# Sheet6.net
KiCad netlist of a schematic drawn in Altium Designer
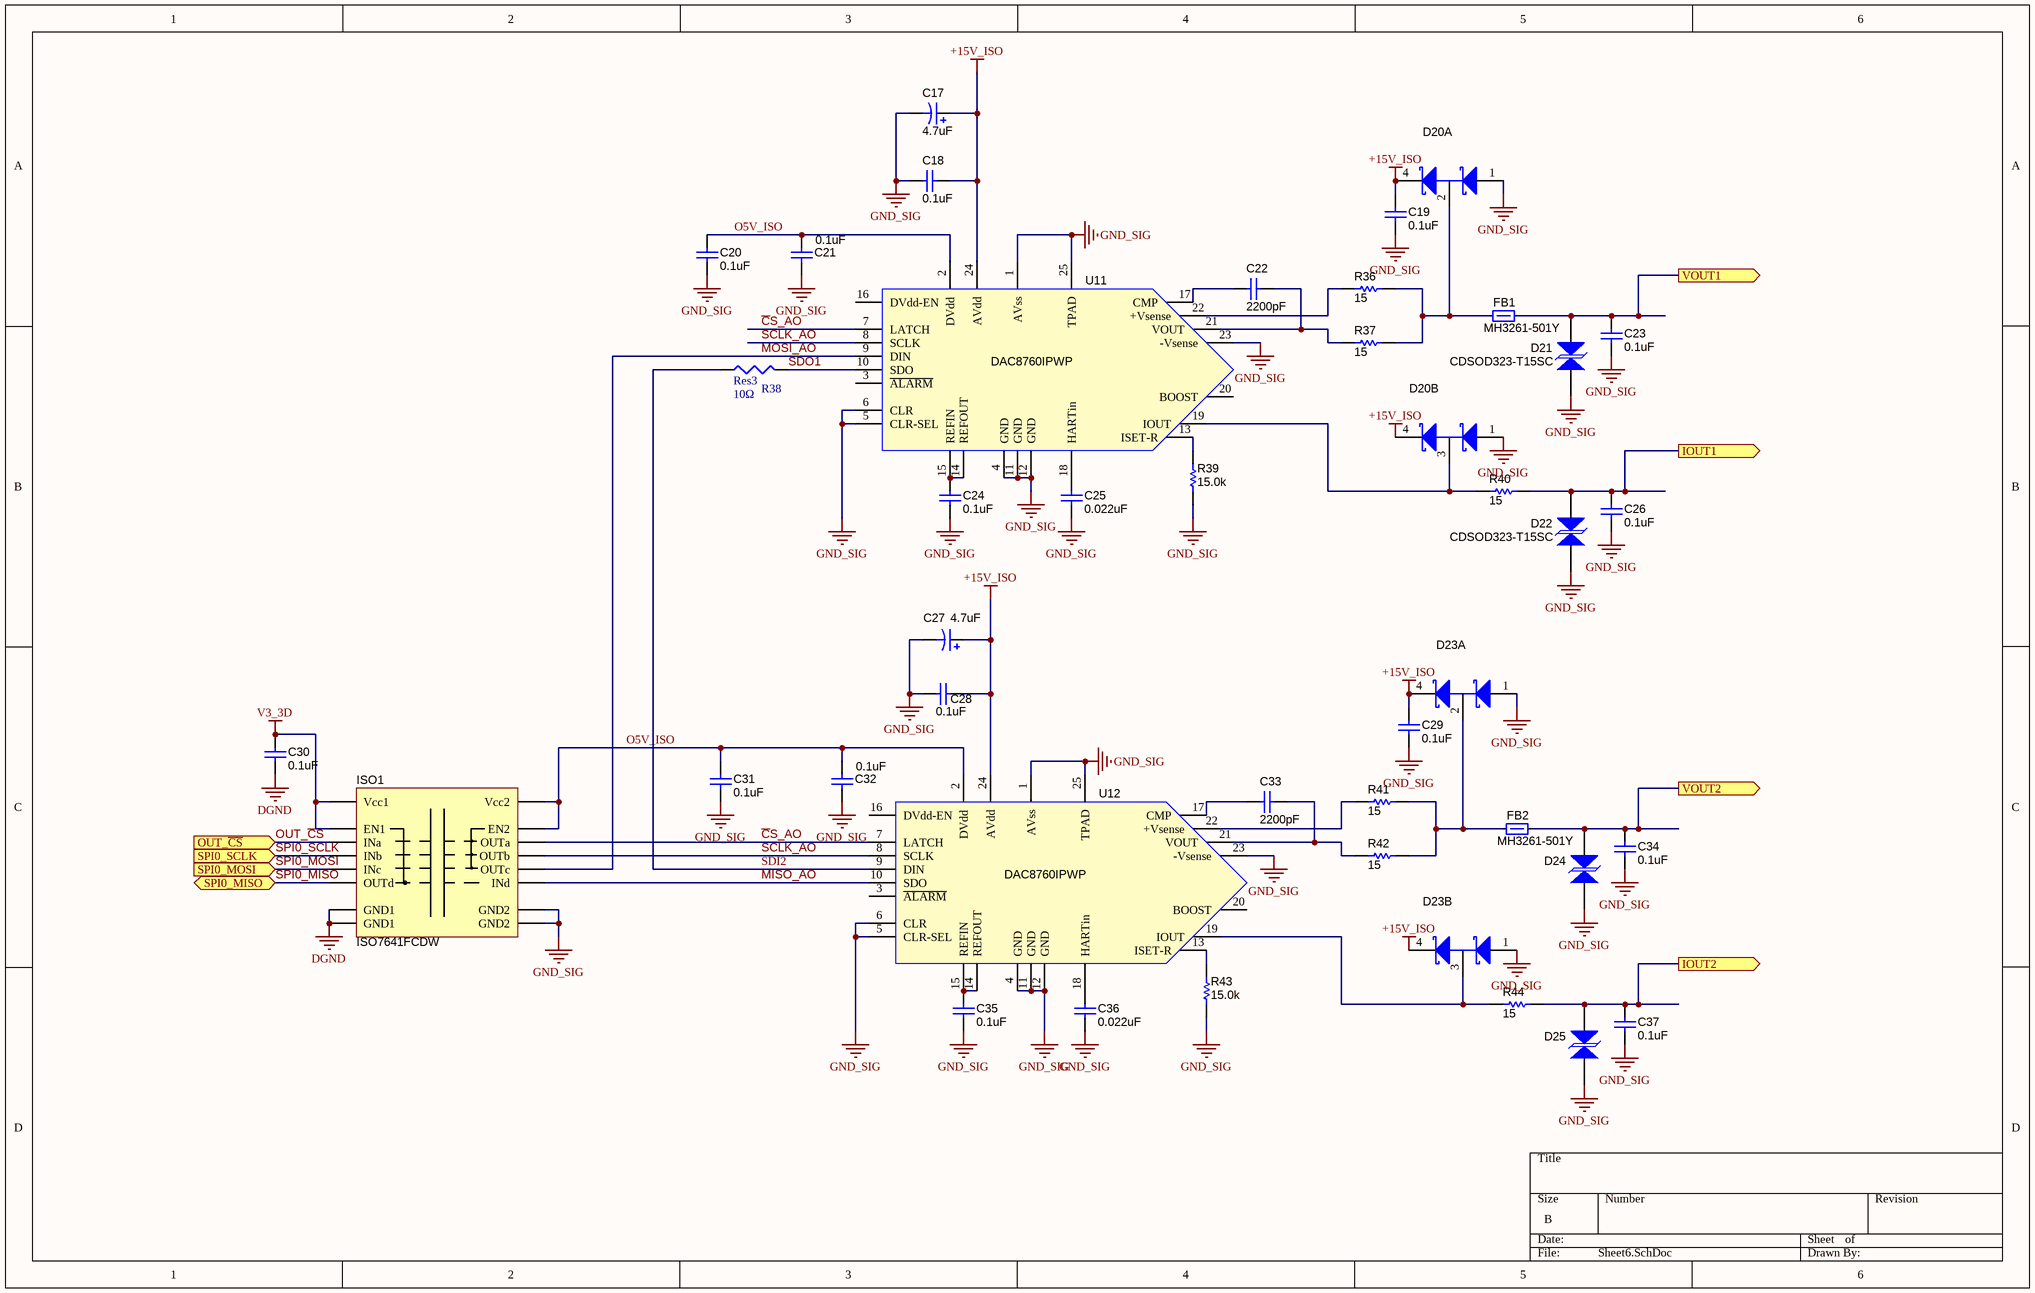
[diagram p0: Sheet6.SchDoc]

(export (version "E")
  (design (tool "Eeschema 10.0.6"))
  (components
    (comp (ref "C17")
      (value "293D475X9035C2TE3")
      (footprint "6032-28")
      (description "CAP, TA, 4.7uF, 35V, +/-10%, 1.9 ohm, SMD")
      (fields
        (field (name "VALUEDISPLAYED") "4.7uF")
        (field (name "MANUFACTURER") "Vishay-Sprague")
        (field (name "PUBLISHER") "Texas Instruments")
      )
      (libsource (lib "Capacitor_Tantalum") (part "293D475X9035C2TE3"))
    )
    (comp (ref "C18")
      (value "GRM188R71H104KA93D")
      (footprint "0805_cap")
      (description "CAP, CERM, 0.1uF, 50V, +/-10%, X7R, 0603")
      (fields
        (field (name "VALUEDISPLAYED") "0.1uF")
        (field (name "MANUFACTURER") "MuRata")
        (field (name "PUBLISHER") "Texas Instruments")
      )
      (libsource (lib "Capacitor_Ceramic") (part "GRM188R71H104KA93D"))
    )
    (comp (ref "C19")
      (value "GRM188R71H104KA93D")
      (footprint "0805_cap")
      (description "CAP, CERM, 0.1uF, 50V, +/-10%, X7R, 0603")
      (fields
        (field (name "VALUEDISPLAYED") "0.1uF")
        (field (name "MANUFACTURER") "MuRata")
        (field (name "PUBLISHER") "Texas Instruments")
      )
      (libsource (lib "Capacitor_Ceramic") (part "GRM188R71H104KA93D"))
    )
    (comp (ref "C20")
      (value "GRM188R71H104KA93D")
      (footprint "0805_cap")
      (description "CAP, CERM, 0.1uF, 50V, +/-10%, X7R, 0603")
      (fields
        (field (name "VALUEDISPLAYED") "0.1uF")
        (field (name "MANUFACTURER") "MuRata")
        (field (name "PUBLISHER") "Texas Instruments")
      )
      (libsource (lib "Capacitor_Ceramic") (part "GRM188R71H104KA93D"))
    )
    (comp (ref "C21")
      (value "GRM188R71H104KA93D")
      (footprint "0805_cap")
      (description "CAP, CERM, 0.1uF, 50V, +/-10%, X7R, 0603")
      (fields
        (field (name "VALUEDISPLAYED") "0.1uF")
        (field (name "MANUFACTURER") "MuRata")
        (field (name "PUBLISHER") "Texas Instruments")
      )
      (libsource (lib "Capacitor_Ceramic") (part "GRM188R71H104KA93D"))
    )
    (comp (ref "C22")
      (value "GRM1885C1H222JA01D")
      (footprint "0805_cap")
      (description "CAP, CERM, 2200pF, 50V, +/-5%, C0G/NP0, 0603")
      (fields
        (field (name "VALUEDISPLAYED") "2200pF")
        (field (name "MANUFACTURER") "MuRata")
        (field (name "PUBLISHER") "Texas Instruments")
      )
      (libsource (lib "Capacitor_Ceramic") (part "GRM1885C1H222JA01D"))
    )
    (comp (ref "C23")
      (value "06035C104KAT2A")
      (footprint "0805_cap")
      (description "CAP, CERM, 0.1uF, 50V, +/-10%, X7R, 0603")
      (fields
        (field (name "VALUEDISPLAYED") "0.1uF")
        (field (name "MANUFACTURER") "AVX")
        (field (name "PUBLISHER") "Texas Instruments")
      )
      (libsource (lib "Capacitor_Ceramic") (part "06035C104KAT2A"))
    )
    (comp (ref "C24")
      (value "06035C104KAT2A")
      (footprint "0805_cap")
      (description "CAP, CERM, 0.1uF, 50V, +/-10%, X7R, 0603")
      (fields
        (field (name "VALUEDISPLAYED") "0.1uF")
        (field (name "MANUFACTURER") "AVX")
        (field (name "PUBLISHER") "Texas Instruments")
      )
      (libsource (lib "Capacitor_Ceramic") (part "06035C104KAT2A"))
    )
    (comp (ref "C25")
      (value "C1608X7R1H223K")
      (footprint "0805_cap")
      (description "CAP, CERM, 0.022uF, 50V, +/-10%, X7R, 0603")
      (fields
        (field (name "VALUEDISPLAYED") "0.022uF")
        (field (name "MANUFACTURER") "TDK")
        (field (name "PUBLISHER") "Texas Instruments")
      )
      (libsource (lib "Capacitor_Ceramic") (part "C1608X7R1H223K"))
    )
    (comp (ref "C26")
      (value "06035C104KAT2A")
      (footprint "0805_cap")
      (description "CAP, CERM, 0.1uF, 50V, +/-10%, X7R, 0603")
      (fields
        (field (name "VALUEDISPLAYED") "0.1uF")
        (field (name "MANUFACTURER") "AVX")
        (field (name "PUBLISHER") "Texas Instruments")
      )
      (libsource (lib "Capacitor_Ceramic") (part "06035C104KAT2A"))
    )
    (comp (ref "C27")
      (value "293D475X9035C2TE3")
      (footprint "6032-28")
      (description "CAP, TA, 4.7uF, 35V, +/-10%, 1.9 ohm, SMD")
      (fields
        (field (name "VALUEDISPLAYED") "4.7uF")
        (field (name "MANUFACTURER") "Vishay-Sprague")
        (field (name "PUBLISHER") "Texas Instruments")
      )
      (libsource (lib "Capacitor_Tantalum") (part "293D475X9035C2TE3"))
    )
    (comp (ref "C28")
      (value "GRM188R71H104KA93D")
      (footprint "0805_cap")
      (description "CAP, CERM, 0.1uF, 50V, +/-10%, X7R, 0603")
      (fields
        (field (name "VALUEDISPLAYED") "0.1uF")
        (field (name "MANUFACTURER") "MuRata")
        (field (name "PUBLISHER") "Texas Instruments")
      )
      (libsource (lib "Capacitor_Ceramic") (part "GRM188R71H104KA93D"))
    )
    (comp (ref "C29")
      (value "GRM188R71H104KA93D")
      (footprint "0805_cap")
      (description "CAP, CERM, 0.1uF, 50V, +/-10%, X7R, 0603")
      (fields
        (field (name "VALUEDISPLAYED") "0.1uF")
        (field (name "MANUFACTURER") "MuRata")
        (field (name "PUBLISHER") "Texas Instruments")
      )
      (libsource (lib "Capacitor_Ceramic") (part "GRM188R71H104KA93D"))
    )
    (comp (ref "C30")
      (value "GRM188R71H104KA93D")
      (footprint "0805_cap")
      (description "CAP, CERM, 0.1uF, 50V, +/-10%, X7R, 0603")
      (fields
        (field (name "VALUEDISPLAYED") "0.1uF")
        (field (name "MANUFACTURER") "MuRata")
        (field (name "PUBLISHER") "Texas Instruments")
      )
      (libsource (lib "Capacitor_Ceramic") (part "GRM188R71H104KA93D"))
    )
    (comp (ref "C31")
      (value "GRM188R71H104KA93D")
      (footprint "0805_cap")
      (description "CAP, CERM, 0.1uF, 50V, +/-10%, X7R, 0603")
      (fields
        (field (name "VALUEDISPLAYED") "0.1uF")
        (field (name "MANUFACTURER") "MuRata")
        (field (name "PUBLISHER") "Texas Instruments")
      )
      (libsource (lib "Capacitor_Ceramic") (part "GRM188R71H104KA93D"))
    )
    (comp (ref "C32")
      (value "GRM188R71H104KA93D")
      (footprint "0805_cap")
      (description "CAP, CERM, 0.1uF, 50V, +/-10%, X7R, 0603")
      (fields
        (field (name "VALUEDISPLAYED") "0.1uF")
        (field (name "MANUFACTURER") "MuRata")
        (field (name "PUBLISHER") "Texas Instruments")
      )
      (libsource (lib "Capacitor_Ceramic") (part "GRM188R71H104KA93D"))
    )
    (comp (ref "C33")
      (value "GRM1885C1H222JA01D")
      (footprint "0805_cap")
      (description "CAP, CERM, 2200pF, 50V, +/-5%, C0G/NP0, 0603")
      (fields
        (field (name "VALUEDISPLAYED") "2200pF")
        (field (name "MANUFACTURER") "MuRata")
        (field (name "PUBLISHER") "Texas Instruments")
      )
      (libsource (lib "Capacitor_Ceramic") (part "GRM1885C1H222JA01D"))
    )
    (comp (ref "C34")
      (value "06035C104KAT2A")
      (footprint "0805_cap")
      (description "CAP, CERM, 0.1uF, 50V, +/-10%, X7R, 0603")
      (fields
        (field (name "VALUEDISPLAYED") "0.1uF")
        (field (name "MANUFACTURER") "AVX")
        (field (name "PUBLISHER") "Texas Instruments")
      )
      (libsource (lib "Capacitor_Ceramic") (part "06035C104KAT2A"))
    )
    (comp (ref "C35")
      (value "06035C104KAT2A")
      (footprint "0805_cap")
      (description "CAP, CERM, 0.1uF, 50V, +/-10%, X7R, 0603")
      (fields
        (field (name "VALUEDISPLAYED") "0.1uF")
        (field (name "MANUFACTURER") "AVX")
        (field (name "PUBLISHER") "Texas Instruments")
      )
      (libsource (lib "Capacitor_Ceramic") (part "06035C104KAT2A"))
    )
    (comp (ref "C36")
      (value "C1608X7R1H223K")
      (footprint "0805_cap")
      (description "CAP, CERM, 0.022uF, 50V, +/-10%, X7R, 0603")
      (fields
        (field (name "VALUEDISPLAYED") "0.022uF")
        (field (name "MANUFACTURER") "TDK")
        (field (name "PUBLISHER") "Texas Instruments")
      )
      (libsource (lib "Capacitor_Ceramic") (part "C1608X7R1H223K"))
    )
    (comp (ref "C37")
      (value "06035C104KAT2A")
      (footprint "0805_cap")
      (description "CAP, CERM, 0.1uF, 50V, +/-10%, X7R, 0603")
      (fields
        (field (name "VALUEDISPLAYED") "0.1uF")
        (field (name "MANUFACTURER") "AVX")
        (field (name "PUBLISHER") "Texas Instruments")
      )
      (libsource (lib "Capacitor_Ceramic") (part "06035C104KAT2A"))
    )
    (comp (ref "D20")
      (value "~")
      (footprint "SOT-143")
      (description "IC TVS ARRAY 2-LINE 70V SOT-143")
      (fields
        (field (name "MANUFACTURER") "Bourns")
        (field (name "PARTNUMBER") "CD143A-SR70")
        (field (name "SYMBOLCREATOR") "Use LDAP id")
      )
      (libsource (lib "DAC8760-Symbols") (part "CD143A-SR70"))
    )
    (comp (ref "D21")
      (value "CDSOD323-T15SC")
      (footprint "sod-323")
      (description "DIODE TVS ARRAY 15V SOD323")
      (fields (field (name "MANUFACTURER") "Bourns") (field (name "SYMBOLCREATOR") "Use LDAP id"))
      (libsource (lib "DAC8760-Symbols") (part "SMAJ15CA"))
    )
    (comp (ref "D22")
      (value "CDSOD323-T15SC")
      (footprint "sod-323")
      (description "DIODE TVS ARRAY 15V SOD323")
      (fields (field (name "MANUFACTURER") "Bourns") (field (name "SYMBOLCREATOR") "Use LDAP id"))
      (libsource (lib "DAC8760-Symbols") (part "SMAJ15CA"))
    )
    (comp (ref "D23")
      (value "~")
      (footprint "SOT-143")
      (description "IC TVS ARRAY 2-LINE 70V SOT-143")
      (fields
        (field (name "MANUFACTURER") "Bourns")
        (field (name "PARTNUMBER") "CD143A-SR70")
        (field (name "SYMBOLCREATOR") "Use LDAP id")
      )
      (libsource (lib "DAC8760-Symbols") (part "CD143A-SR70"))
    )
    (comp (ref "D24")
      (value "~")
      (footprint "sod-323")
      (description "DIODE TVS ARRAY 15V SOD323")
      (fields
        (field (name "MANUFACTURER") "Bourns")
        (field (name "PARTNUMBER") "CDSOD323-T15SC")
        (field (name "SYMBOLCREATOR") "Use LDAP id")
      )
      (libsource (lib "DAC8760-Symbols") (part "SMAJ15CA"))
    )
    (comp (ref "D25")
      (value "~")
      (footprint "sod-323")
      (description "DIODE TVS ARRAY 15V SOD323")
      (fields
        (field (name "MANUFACTURER") "Bourns")
        (field (name "PARTNUMBER") "CDSOD323-T15SC")
        (field (name "SYMBOLCREATOR") "Use LDAP id")
      )
      (libsource (lib "DAC8760-Symbols") (part "SMAJ15CA"))
    )
    (comp (ref "FB1")
      (value "MH3261-501Y")
      (footprint "1210")
      (description "BEAD FERRITE 500 OHM 3.0A 3216")
      (fields (field (name "MANUFACTURER") "Bourns Inc.") (field (name "PUBLISHER") "Texas Instruments"))
      (libsource (lib "MiscParts") (part "Ferrite_Bead"))
    )
    (comp (ref "FB2")
      (value "MH3261-501Y")
      (footprint "1210")
      (description "BEAD FERRITE 500 OHM 3.0A 3216")
      (fields (field (name "MANUFACTURER") "Bourns Inc.") (field (name "PUBLISHER") "Texas Instruments"))
      (libsource (lib "MiscParts") (part "Ferrite_Bead"))
    )
    (comp (ref "ISO1")
      (value "ISO7641FCDW")
      (footprint "M16B_N")
      (description "ISOLATOR DGTL 25MBPS 4CH 16SOIC")
      (fields
        (field (name "MANUFACTURER") "Texas Instruments Inc")
        (field (name "SYMBOLCREATOR") "Use LDAP id")
      )
      (libsource (lib "DAC8760-Symbols") (part "ISO7241"))
    )
    (comp (ref "R36")
      (value "15")
      (footprint "0805")
      (description "RES, 15 ohm, 5%, 0.1W, 0603")
      (fields
        (field (name "PARTNUMBER") "CRCW060315R0JNEA")
        (field (name "MANUFACTURER") "Vishay-Dale")
        (field (name "PUBLISHER") "Texas Instruments")
      )
      (libsource (lib "Resistor_0603") (part "CRCW060315R0JNEA"))
    )
    (comp (ref "R37")
      (value "15")
      (footprint "0805")
      (description "RES, 15 ohm, 5%, 0.1W, 0603")
      (fields
        (field (name "PARTNUMBER") "CRCW060315R0JNEA")
        (field (name "MANUFACTURER") "Vishay-Dale")
        (field (name "PUBLISHER") "Texas Instruments")
      )
      (libsource (lib "Resistor_0603") (part "CRCW060315R0JNEA"))
    )
    (comp (ref "R38")
      (value "Res3")
      (footprint "0805")
      (description "Resistor")
      (fields (field (name "ALTIUM_VALUE") "10Ω") (field (name "PUBLISHER") "Altium Limited"))
      (libsource (lib "Miscellaneous Devices") (part "Res3"))
    )
    (comp (ref "R39")
      (value "15.0k")
      (footprint "0805")
      (description "RES, 15.0k ohm, 0.1%, 0.1W, 0603")
      (fields
        (field (name "PARTNUMBER") "RT0603BRD0715KL")
        (field (name "MANUFACTURER") "Yageo America")
        (field (name "PUBLISHER") "Texas Instruments")
      )
      (libsource (lib "Resistor_0603") (part "RT0603BRD0715KL"))
    )
    (comp (ref "R40")
      (value "15")
      (footprint "1210")
      (description "RES 15 OHM 1W 5% 2512")
      (fields
        (field (name "PARTNUMBER") "RPC2512JT15R0")
        (field (name "MANUFACTURER") "Stackpole Electronics")
      )
      (libsource (lib "Resistor_OtherSMT") (part "CRA2512-FZ-R080ELF"))
    )
    (comp (ref "R41")
      (value "15")
      (footprint "0805")
      (description "RES, 15 ohm, 5%, 0.1W, 0603")
      (fields
        (field (name "PARTNUMBER") "CRCW060315R0JNEA")
        (field (name "MANUFACTURER") "Vishay-Dale")
        (field (name "PUBLISHER") "Texas Instruments")
      )
      (libsource (lib "Resistor_0603") (part "CRCW060315R0JNEA"))
    )
    (comp (ref "R42")
      (value "15")
      (footprint "0805")
      (description "RES, 15 ohm, 5%, 0.1W, 0603")
      (fields
        (field (name "PARTNUMBER") "CRCW060315R0JNEA")
        (field (name "MANUFACTURER") "Vishay-Dale")
        (field (name "PUBLISHER") "Texas Instruments")
      )
      (libsource (lib "Resistor_0603") (part "CRCW060315R0JNEA"))
    )
    (comp (ref "R43")
      (value "15.0k")
      (footprint "0805")
      (description "RES, 15.0k ohm, 0.1%, 0.1W, 0603")
      (fields
        (field (name "PARTNUMBER") "RT0603BRD0715KL")
        (field (name "MANUFACTURER") "Yageo America")
        (field (name "PUBLISHER") "Texas Instruments")
      )
      (libsource (lib "Resistor_0603") (part "RT0603BRD0715KL"))
    )
    (comp (ref "R44")
      (value "15")
      (footprint "1210")
      (description "RES 15 OHM 1W 5% 2512")
      (fields
        (field (name "PARTNUMBER") "RPC2512JT15R0")
        (field (name "MANUFACTURER") "Stackpole Electronics")
      )
      (libsource (lib "Resistor_OtherSMT") (part "CRA2512-FZ-R080ELF"))
    )
    (comp (ref "U11")
      (value "DAC8760IPWP")
      (footprint "PWP24-DIE84X166")
      (description "1-Channel, 16-Bit, Programmable Current/Voltage Output DAC for 4-20mA Current Loop Applications")
      (fields
        (field (name "MANUFACTURER") "Texas Instruments")
        (field (name "SYMBOLCREATOR") "x0120606")
        (field (name "PUBLISHER") "Texas Instruments")
      )
      (libsource (lib "dolphi_ecs") (part "DAC8760IPWP_1"))
    )
    (comp (ref "U12")
      (value "DAC8760IPWP")
      (footprint "PWP24-DIE84X166")
      (description "1-Channel, 16-Bit, Programmable Current/Voltage Output DAC for 4-20mA Current Loop Applications")
      (fields
        (field (name "MANUFACTURER") "Texas Instruments")
        (field (name "SYMBOLCREATOR") "x0120606")
        (field (name "PUBLISHER") "Texas Instruments")
      )
      (libsource (lib "dolphi_ecs") (part "DAC8760IPWP_1"))
    )
  )
  (nets
    (net (code "1") (name "+15V_ISO") (class "Default")
      (node (ref "C17") (pin "1") (pinfunction "+_1") (pintype "passive"))
      (node (ref "C18") (pin "1") (pinfunction "1_1") (pintype "passive"))
      (node (ref "C19") (pin "1") (pinfunction "1_1") (pintype "passive"))
      (node (ref "C27") (pin "1") (pinfunction "+_1") (pintype "passive"))
      (node (ref "C28") (pin "1") (pinfunction "1_1") (pintype "passive"))
      (node (ref "C29") (pin "1") (pinfunction "1_1") (pintype "passive"))
      (node (ref "D20") (pin "4") (pinfunction "4_4") (pintype "passive"))
      (node (ref "D23") (pin "4") (pinfunction "4_4") (pintype "passive"))
      (node (ref "U11") (pin "24") (pinfunction "AVdd_24") (pintype "passive"))
      (node (ref "U12") (pin "24") (pinfunction "AVdd_24") (pintype "passive"))
    )
    (net (code "2") (name "/IOUT1") (class "Default")
      (node (ref "C26") (pin "1") (pinfunction "1_1") (pintype "passive"))
      (node (ref "D22") (pin "1") (pinfunction "1_1") (pintype "passive"))
      (node (ref "R40") (pin "2") (pinfunction "2_2") (pintype "passive"))
    )
    (net (code "3") (name "/IOUT2") (class "Default")
      (node (ref "C37") (pin "1") (pinfunction "1_1") (pintype "passive"))
      (node (ref "D25") (pin "1") (pinfunction "1_1") (pintype "passive"))
      (node (ref "R44") (pin "2") (pinfunction "2_2") (pintype "passive"))
    )
    (net (code "4") (name "/MISO_AO") (class "Default")
      (node (ref "ISO1") (pin "11") (pinfunction "INd_11") (pintype "passive"))
      (node (ref "U12") (pin "10") (pinfunction "SDO_10") (pintype "passive"))
    )
    (net (code "5") (name "/MOSI_AO") (class "Default")
      (node (ref "ISO1") (pin "12") (pinfunction "OUTc_12") (pintype "passive"))
      (node (ref "U11") (pin "9") (pinfunction "DIN_9") (pintype "passive"))
    )
    (net (code "6") (name "/O5V_ISO") (class "Default")
      (node (ref "C20") (pin "1") (pinfunction "1_1") (pintype "passive"))
      (node (ref "C21") (pin "1") (pinfunction "1_1") (pintype "passive"))
      (node (ref "C31") (pin "1") (pinfunction "1_1") (pintype "passive"))
      (node (ref "C32") (pin "1") (pinfunction "1_1") (pintype "passive"))
      (node (ref "ISO1") (pin "10") (pinfunction "EN2_10") (pintype "passive"))
      (node (ref "ISO1") (pin "16") (pinfunction "Vcc2_16") (pintype "passive"))
      (node (ref "U11") (pin "2") (pinfunction "DVdd_2") (pintype "passive"))
      (node (ref "U12") (pin "2") (pinfunction "DVdd_2") (pintype "passive"))
    )
    (net (code "7") (name "/OUT_~{CS}") (class "Default")
      (node (ref "ISO1") (pin "3") (pinfunction "INa_3") (pintype "passive"))
    )
    (net (code "8") (name "/SCLK_AO") (class "Default")
      (node (ref "ISO1") (pin "13") (pinfunction "OUTb_13") (pintype "passive"))
      (node (ref "U11") (pin "8") (pinfunction "SCLK_8") (pintype "passive"))
      (node (ref "U12") (pin "8") (pinfunction "SCLK_8") (pintype "passive"))
    )
    (net (code "9") (name "/SDI2") (class "Default")
      (node (ref "R38") (pin "1") (pinfunction "1_1") (pintype "passive"))
      (node (ref "U12") (pin "9") (pinfunction "DIN_9") (pintype "passive"))
    )
    (net (code "10") (name "/SDO1") (class "Default")
      (node (ref "R38") (pin "2") (pinfunction "2_2") (pintype "passive"))
      (node (ref "U11") (pin "10") (pinfunction "SDO_10") (pintype "passive"))
    )
    (net (code "11") (name "/SPI0_MISO") (class "Default")
      (node (ref "ISO1") (pin "6") (pinfunction "OUTd_6") (pintype "passive"))
    )
    (net (code "12") (name "/SPI0_MOSI") (class "Default")
      (node (ref "ISO1") (pin "5") (pinfunction "INc_5") (pintype "passive"))
    )
    (net (code "13") (name "/SPI0_SCLK") (class "Default")
      (node (ref "ISO1") (pin "4") (pinfunction "INb_4") (pintype "passive"))
    )
    (net (code "14") (name "/VOUT1") (class "Default")
      (node (ref "C23") (pin "1") (pinfunction "1_1") (pintype "passive"))
      (node (ref "D21") (pin "1") (pinfunction "1_1") (pintype "passive"))
      (node (ref "FB1") (pin "2") (pinfunction "2_2") (pintype "passive"))
    )
    (net (code "15") (name "/VOUT2") (class "Default")
      (node (ref "C34") (pin "1") (pinfunction "1_1") (pintype "passive"))
      (node (ref "D24") (pin "1") (pinfunction "1_1") (pintype "passive"))
      (node (ref "FB2") (pin "2") (pinfunction "2_2") (pintype "passive"))
    )
    (net (code "16") (name "/~{C}S_AO") (class "Default")
      (node (ref "ISO1") (pin "14") (pinfunction "OUTa_14") (pintype "passive"))
      (node (ref "U11") (pin "7") (pinfunction "LATCH_7") (pintype "passive"))
      (node (ref "U12") (pin "7") (pinfunction "LATCH_7") (pintype "passive"))
    )
    (net (code "17") (name "DGND") (class "Default")
      (node (ref "C30") (pin "2") (pinfunction "2_2") (pintype "passive"))
      (node (ref "ISO1") (pin "2") (pinfunction "GND1_2") (pintype "passive"))
      (node (ref "ISO1") (pin "8") (pinfunction "GND1_8") (pintype "passive"))
    )
    (net (code "18") (name "GND_SIG") (class "Default")
      (node (ref "C17") (pin "2") (pinfunction "-_2") (pintype "passive"))
      (node (ref "C18") (pin "2") (pinfunction "2_2") (pintype "passive"))
      (node (ref "C19") (pin "2") (pinfunction "2_2") (pintype "passive"))
      (node (ref "C20") (pin "2") (pinfunction "2_2") (pintype "passive"))
      (node (ref "C21") (pin "2") (pinfunction "2_2") (pintype "passive"))
      (node (ref "C23") (pin "2") (pinfunction "2_2") (pintype "passive"))
      (node (ref "C24") (pin "2") (pinfunction "2_2") (pintype "passive"))
      (node (ref "C25") (pin "2") (pinfunction "2_2") (pintype "passive"))
      (node (ref "C26") (pin "2") (pinfunction "2_2") (pintype "passive"))
      (node (ref "C27") (pin "2") (pinfunction "-_2") (pintype "passive"))
      (node (ref "C28") (pin "2") (pinfunction "2_2") (pintype "passive"))
      (node (ref "C29") (pin "2") (pinfunction "2_2") (pintype "passive"))
      (node (ref "C31") (pin "2") (pinfunction "2_2") (pintype "passive"))
      (node (ref "C32") (pin "2") (pinfunction "2_2") (pintype "passive"))
      (node (ref "C34") (pin "2") (pinfunction "2_2") (pintype "passive"))
      (node (ref "C35") (pin "2") (pinfunction "2_2") (pintype "passive"))
      (node (ref "C36") (pin "2") (pinfunction "2_2") (pintype "passive"))
      (node (ref "C37") (pin "2") (pinfunction "2_2") (pintype "passive"))
      (node (ref "D20") (pin "1") (pinfunction "1_1") (pintype "passive"))
      (node (ref "D21") (pin "2") (pinfunction "2_2") (pintype "passive"))
      (node (ref "D22") (pin "2") (pinfunction "2_2") (pintype "passive"))
      (node (ref "D23") (pin "1") (pinfunction "1_1") (pintype "passive"))
      (node (ref "D24") (pin "2") (pinfunction "2_2") (pintype "passive"))
      (node (ref "D25") (pin "2") (pinfunction "2_2") (pintype "passive"))
      (node (ref "ISO1") (pin "15") (pinfunction "GND2_15") (pintype "passive"))
      (node (ref "ISO1") (pin "9") (pinfunction "GND2_9") (pintype "passive"))
      (node (ref "R39") (pin "1") (pinfunction "1_1") (pintype "passive"))
      (node (ref "R43") (pin "1") (pinfunction "1_1") (pintype "passive"))
      (node (ref "U11") (pin "1") (pinfunction "AVss_1") (pintype "passive"))
      (node (ref "U11") (pin "11") (pinfunction "GND_11") (pintype "passive"))
      (node (ref "U11") (pin "12") (pinfunction "GND_12") (pintype "passive"))
      (node (ref "U11") (pin "23") (pinfunction "-Vsense_23") (pintype "passive"))
      (node (ref "U11") (pin "25") (pinfunction "TPAD_25") (pintype "passive"))
      (node (ref "U11") (pin "4") (pinfunction "GND_4") (pintype "passive"))
      (node (ref "U11") (pin "5") (pinfunction "CLR-SEL_5") (pintype "passive"))
      (node (ref "U11") (pin "6") (pinfunction "CLR_6") (pintype "passive"))
      (node (ref "U12") (pin "1") (pinfunction "AVss_1") (pintype "passive"))
      (node (ref "U12") (pin "11") (pinfunction "GND_11") (pintype "passive"))
      (node (ref "U12") (pin "12") (pinfunction "GND_12") (pintype "passive"))
      (node (ref "U12") (pin "23") (pinfunction "-Vsense_23") (pintype "passive"))
      (node (ref "U12") (pin "25") (pinfunction "TPAD_25") (pintype "passive"))
      (node (ref "U12") (pin "4") (pinfunction "GND_4") (pintype "passive"))
      (node (ref "U12") (pin "5") (pinfunction "CLR-SEL_5") (pintype "passive"))
      (node (ref "U12") (pin "6") (pinfunction "CLR_6") (pintype "passive"))
    )
    (net (code "19") (name "Net-(D20-Pad2)") (class "Default")
      (node (ref "D20") (pin "2") (pinfunction "2_2") (pintype "passive"))
      (node (ref "FB1") (pin "1") (pinfunction "1_1") (pintype "passive"))
      (node (ref "R36") (pin "2") (pinfunction "2_2") (pintype "passive"))
      (node (ref "R37") (pin "2") (pinfunction "2_2") (pintype "passive"))
    )
    (net (code "20") (name "Net-(D23-Pad2)") (class "Default")
      (node (ref "D23") (pin "2") (pinfunction "2_2") (pintype "passive"))
      (node (ref "FB2") (pin "1") (pinfunction "1_1") (pintype "passive"))
      (node (ref "R41") (pin "2") (pinfunction "2_2") (pintype "passive"))
      (node (ref "R42") (pin "2") (pinfunction "2_2") (pintype "passive"))
    )
    (net (code "21") (name "Net-(U11-+Vsense)") (class "Default")
      (node (ref "R36") (pin "1") (pinfunction "1_1") (pintype "passive"))
      (node (ref "U11") (pin "22") (pinfunction "+Vsense_22") (pintype "passive"))
    )
    (net (code "22") (name "Net-(U11-CMP)") (class "Default")
      (node (ref "C22") (pin "2") (pinfunction "2_2") (pintype "passive"))
      (node (ref "U11") (pin "17") (pinfunction "CMP_17") (pintype "passive"))
    )
    (net (code "23") (name "Net-(U11-HARTin)") (class "Default")
      (node (ref "C25") (pin "1") (pinfunction "1_1") (pintype "passive"))
      (node (ref "U11") (pin "18") (pinfunction "HARTin_18") (pintype "passive"))
    )
    (net (code "24") (name "Net-(U11-IOUT)") (class "Default")
      (node (ref "D20") (pin "3") (pinfunction "3_3") (pintype "passive"))
      (node (ref "R40") (pin "1") (pinfunction "1_1") (pintype "passive"))
      (node (ref "U11") (pin "19") (pinfunction "IOUT_19") (pintype "passive"))
    )
    (net (code "25") (name "Net-(U11-ISET-R)") (class "Default")
      (node (ref "R39") (pin "2") (pinfunction "2_2") (pintype "passive"))
      (node (ref "U11") (pin "13") (pinfunction "ISET-R_13") (pintype "passive"))
    )
    (net (code "26") (name "Net-(U11-REFIN)") (class "Default")
      (node (ref "C24") (pin "1") (pinfunction "1_1") (pintype "passive"))
      (node (ref "U11") (pin "14") (pinfunction "REFOUT_14") (pintype "passive"))
      (node (ref "U11") (pin "15") (pinfunction "REFIN_15") (pintype "passive"))
    )
    (net (code "27") (name "Net-(U11-VOUT)") (class "Default")
      (node (ref "C22") (pin "1") (pinfunction "1_1") (pintype "passive"))
      (node (ref "R37") (pin "1") (pinfunction "1_1") (pintype "passive"))
      (node (ref "U11") (pin "21") (pinfunction "VOUT_21") (pintype "passive"))
    )
    (net (code "28") (name "Net-(U12-+Vsense)") (class "Default")
      (node (ref "R41") (pin "1") (pinfunction "1_1") (pintype "passive"))
      (node (ref "U12") (pin "22") (pinfunction "+Vsense_22") (pintype "passive"))
    )
    (net (code "29") (name "Net-(U12-CMP)") (class "Default")
      (node (ref "C33") (pin "2") (pinfunction "2_2") (pintype "passive"))
      (node (ref "U12") (pin "17") (pinfunction "CMP_17") (pintype "passive"))
    )
    (net (code "30") (name "Net-(U12-HARTin)") (class "Default")
      (node (ref "C36") (pin "1") (pinfunction "1_1") (pintype "passive"))
      (node (ref "U12") (pin "18") (pinfunction "HARTin_18") (pintype "passive"))
    )
    (net (code "31") (name "Net-(U12-IOUT)") (class "Default")
      (node (ref "D23") (pin "3") (pinfunction "3_3") (pintype "passive"))
      (node (ref "R44") (pin "1") (pinfunction "1_1") (pintype "passive"))
      (node (ref "U12") (pin "19") (pinfunction "IOUT_19") (pintype "passive"))
    )
    (net (code "32") (name "Net-(U12-ISET-R)") (class "Default")
      (node (ref "R43") (pin "2") (pinfunction "2_2") (pintype "passive"))
      (node (ref "U12") (pin "13") (pinfunction "ISET-R_13") (pintype "passive"))
    )
    (net (code "33") (name "Net-(U12-REFIN)") (class "Default")
      (node (ref "C35") (pin "1") (pinfunction "1_1") (pintype "passive"))
      (node (ref "U12") (pin "14") (pinfunction "REFOUT_14") (pintype "passive"))
      (node (ref "U12") (pin "15") (pinfunction "REFIN_15") (pintype "passive"))
    )
    (net (code "34") (name "Net-(U12-VOUT)") (class "Default")
      (node (ref "C33") (pin "1") (pinfunction "1_1") (pintype "passive"))
      (node (ref "R42") (pin "1") (pinfunction "1_1") (pintype "passive"))
      (node (ref "U12") (pin "21") (pinfunction "VOUT_21") (pintype "passive"))
    )
    (net (code "35") (name "V3_3D") (class "Default")
      (node (ref "C30") (pin "1") (pinfunction "1_1") (pintype "passive"))
      (node (ref "ISO1") (pin "1") (pinfunction "Vcc1_1") (pintype "passive"))
      (node (ref "ISO1") (pin "7") (pinfunction "EN1_7") (pintype "passive"))
    )
    (net (code "36") (name "unconnected-(U11-BOOST-Pad20)") (class "Default")
      (node (ref "U11") (pin "20") (pinfunction "BOOST_20") (pintype "passive"))
    )
    (net (code "37") (name "unconnected-(U11-DVdd-EN-Pad16)") (class "Default")
      (node (ref "U11") (pin "16") (pinfunction "DVdd-EN_16") (pintype "passive"))
    )
    (net (code "38") (name "unconnected-(U11-~{ALARM}-Pad3)") (class "Default")
      (node (ref "U11") (pin "3") (pinfunction "~{ALARM}_3") (pintype "passive"))
    )
    (net (code "39") (name "unconnected-(U12-BOOST-Pad20)") (class "Default")
      (node (ref "U12") (pin "20") (pinfunction "BOOST_20") (pintype "passive"))
    )
    (net (code "40") (name "unconnected-(U12-DVdd-EN-Pad16)") (class "Default")
      (node (ref "U12") (pin "16") (pinfunction "DVdd-EN_16") (pintype "passive"))
    )
    (net (code "41") (name "unconnected-(U12-~{ALARM}-Pad3)") (class "Default")
      (node (ref "U12") (pin "3") (pinfunction "~{ALARM}_3") (pintype "passive"))
    )
  )
)
